# stm32.net
KiCad netlist of a schematic drawn in Altium Designer
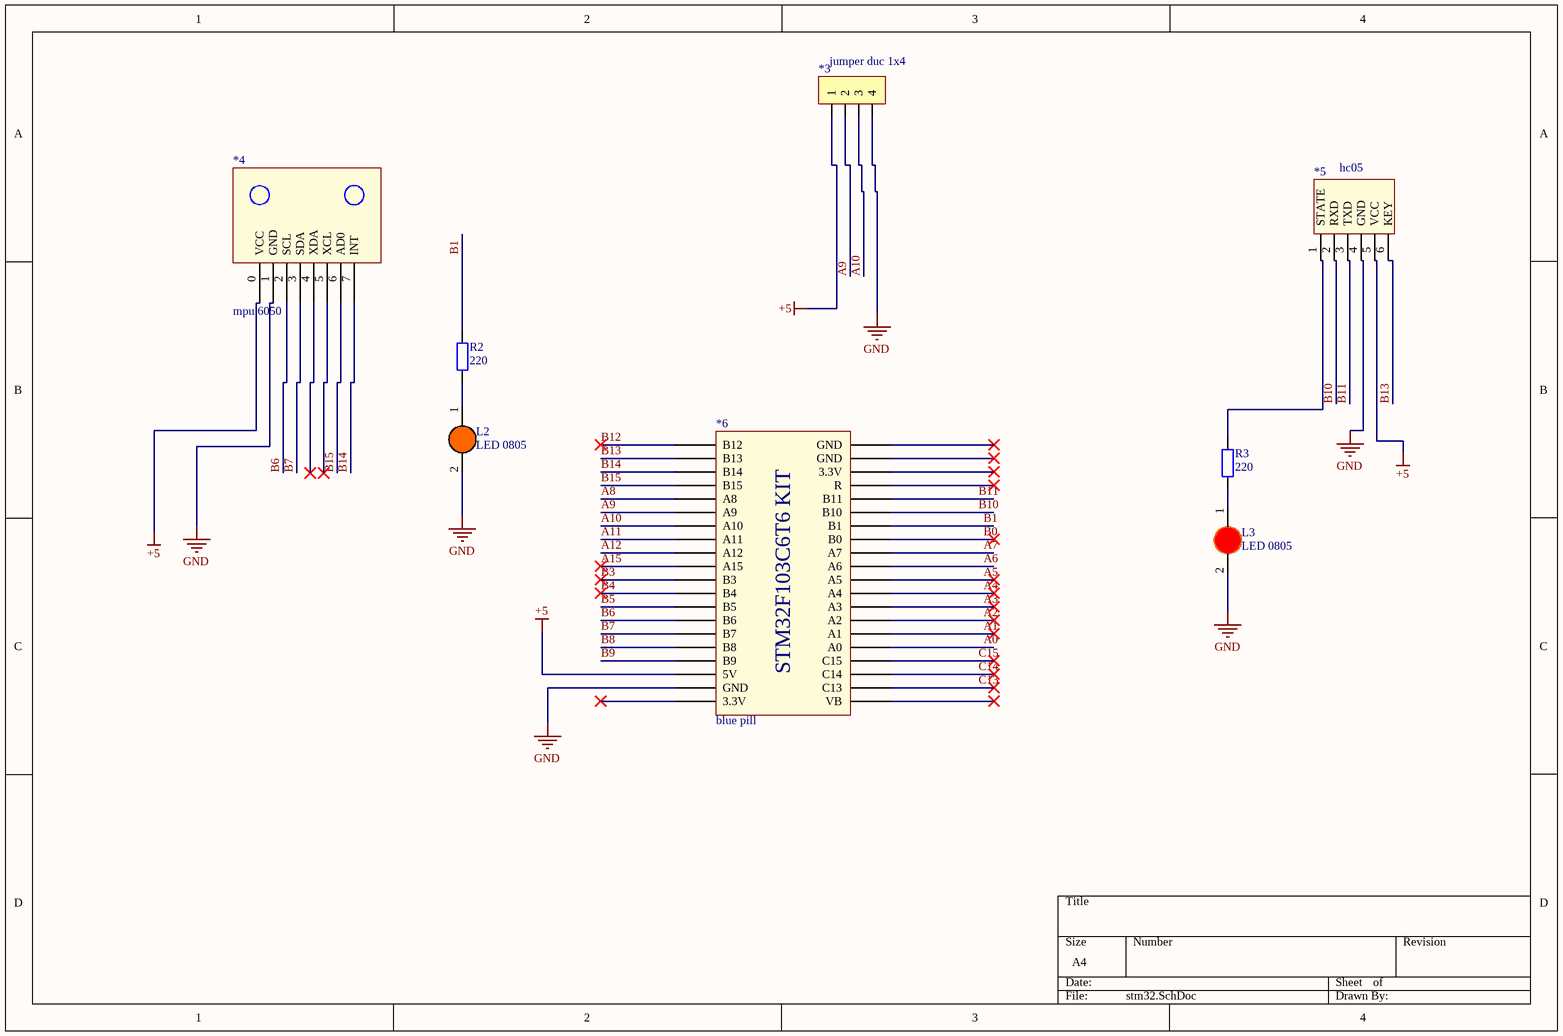
[diagram p0: stm32.SchDoc]

(export (version "E")
  (design (tool "Eeschema 10.0.6"))
  (components
    (comp (ref "*3")
      (value "jumper duc 1x4")
      (footprint "jumper cai 1x4")
      (libsource (lib "my_lib") (part "jumper duc 1x4"))
    )
    (comp (ref "*4") (value "mpu 6050") (footprint "MPU 6050") (libsource (lib "my_lib") (part "mpu 6050")))
    (comp (ref "*5") (value "hc05") (footprint "HC05") (libsource (lib "my_lib") (part "hc05")))
    (comp (ref "*6")
      (value "blue pill")
      (footprint "blue pill")
      (libsource (lib "my_lib") (part "blue pill"))
    )
    (comp (ref "L2")
      (value "LED 0805")
      (footprint "LED-0805-Orange")
      (description "Dán")
      (libsource (lib "Altium_Lib_by_KhueNguyenCreator") (part "LED 0805 Cam"))
    )
    (comp (ref "L3")
      (value "LED 0805")
      (footprint "LED-0805-Red")
      (description "Dán")
      (libsource (lib "Altium_Lib_by_KhueNguyenCreator") (part "LED 0805 Do"))
    )
    (comp (ref "R2")
      (value "220")
      (footprint "tro smd 0805")
      (description "Dán")
      (libsource (lib "Altium_Lib_by_KhueNguyenCreator") (part "Tro 0805 1% 1k"))
    )
    (comp (ref "R3")
      (value "220")
      (footprint "tro smd 0805")
      (description "Dán")
      (libsource (lib "Altium_Lib_by_KhueNguyenCreator") (part "Tro 0805 1% 1k"))
    )
  )
  (nets
    (net (code "1") (name "+5") (class "Default")
      (node (ref "*3") (pin "1") (pinfunction "1_1") (pintype "passive"))
      (node (ref "*4") (pin "0") (pinfunction "VCC_0") (pintype "passive"))
      (node (ref "*5") (pin "5") (pinfunction "VCC_5") (pintype "passive"))
      (node (ref "*6") (pin "18") (pinfunction "5V_18") (pintype "passive"))
    )
    (net (code "2") (name "/A0") (class "Default")
      (node (ref "*6") (pin "25") (pinfunction "A0_25") (pintype "passive"))
    )
    (net (code "3") (name "/A1") (class "Default")
      (node (ref "*6") (pin "26") (pinfunction "A1_26") (pintype "passive+no_connect"))
    )
    (net (code "4") (name "/A2") (class "Default")
      (node (ref "*6") (pin "27") (pinfunction "A2_27") (pintype "passive+no_connect"))
    )
    (net (code "5") (name "/A3") (class "Default")
      (node (ref "*6") (pin "28") (pinfunction "A3_28") (pintype "passive+no_connect"))
    )
    (net (code "6") (name "/A4") (class "Default")
      (node (ref "*6") (pin "29") (pinfunction "A4_29") (pintype "passive+no_connect"))
    )
    (net (code "7") (name "/A5") (class "Default")
      (node (ref "*6") (pin "30") (pinfunction "A5_30") (pintype "passive+no_connect"))
    )
    (net (code "8") (name "/A6") (class "Default")
      (node (ref "*6") (pin "31") (pinfunction "A6_31") (pintype "passive"))
    )
    (net (code "9") (name "/A7") (class "Default")
      (node (ref "*6") (pin "32") (pinfunction "A7_32") (pintype "passive"))
    )
    (net (code "10") (name "/A8") (class "Default")
      (node (ref "*6") (pin "5") (pinfunction "A8_5") (pintype "passive"))
    )
    (net (code "11") (name "/A9") (class "Default")
      (node (ref "*3") (pin "2") (pinfunction "2_2") (pintype "passive"))
      (node (ref "*6") (pin "6") (pinfunction "A9_6") (pintype "passive"))
    )
    (net (code "12") (name "/A10") (class "Default")
      (node (ref "*3") (pin "3") (pinfunction "3_3") (pintype "passive"))
      (node (ref "*6") (pin "7") (pinfunction "A10_7") (pintype "passive"))
    )
    (net (code "13") (name "/A11") (class "Default")
      (node (ref "*6") (pin "8") (pinfunction "A11_8") (pintype "passive"))
    )
    (net (code "14") (name "/A12") (class "Default")
      (node (ref "*6") (pin "9") (pinfunction "A12_9") (pintype "passive"))
    )
    (net (code "15") (name "/A15") (class "Default")
      (node (ref "*6") (pin "10") (pinfunction "A15_10") (pintype "passive+no_connect"))
    )
    (net (code "16") (name "/B0") (class "Default")
      (node (ref "*6") (pin "33") (pinfunction "B0_33") (pintype "passive+no_connect"))
    )
    (net (code "17") (name "/B1") (class "Default")
      (node (ref "*6") (pin "34") (pinfunction "B1_34") (pintype "passive"))
      (node (ref "R2") (pin "2") (pinfunction "2_2") (pintype "passive"))
    )
    (net (code "18") (name "/B3") (class "Default")
      (node (ref "*6") (pin "11") (pinfunction "B3_11") (pintype "passive+no_connect"))
    )
    (net (code "19") (name "/B4") (class "Default")
      (node (ref "*6") (pin "12") (pinfunction "B4_12") (pintype "passive+no_connect"))
    )
    (net (code "20") (name "/B5") (class "Default")
      (node (ref "*6") (pin "13") (pinfunction "B5_13") (pintype "passive"))
    )
    (net (code "21") (name "/B6") (class "Default")
      (node (ref "*4") (pin "2") (pinfunction "SCL_2") (pintype "passive"))
      (node (ref "*6") (pin "14") (pinfunction "B6_14") (pintype "passive"))
    )
    (net (code "22") (name "/B7") (class "Default")
      (node (ref "*4") (pin "3") (pinfunction "SDA_3") (pintype "passive"))
      (node (ref "*6") (pin "15") (pinfunction "B7_15") (pintype "passive"))
    )
    (net (code "23") (name "/B8") (class "Default")
      (node (ref "*6") (pin "16") (pinfunction "B8_16") (pintype "passive"))
    )
    (net (code "24") (name "/B9") (class "Default")
      (node (ref "*6") (pin "17") (pinfunction "B9_17") (pintype "passive"))
    )
    (net (code "25") (name "/B10") (class "Default")
      (node (ref "*5") (pin "2") (pinfunction "RXD_2") (pintype "passive"))
      (node (ref "*6") (pin "35") (pinfunction "B10_35") (pintype "passive"))
    )
    (net (code "26") (name "/B11") (class "Default")
      (node (ref "*5") (pin "3") (pinfunction "TXD_3") (pintype "passive"))
      (node (ref "*6") (pin "36") (pinfunction "B11_36") (pintype "passive"))
    )
    (net (code "27") (name "/B12") (class "Default")
      (node (ref "*6") (pin "1") (pinfunction "B12_1") (pintype "passive+no_connect"))
    )
    (net (code "28") (name "/B13") (class "Default")
      (node (ref "*5") (pin "6") (pinfunction "KEY_6") (pintype "passive"))
      (node (ref "*6") (pin "2") (pinfunction "B13_2") (pintype "passive"))
    )
    (net (code "29") (name "/B14") (class "Default")
      (node (ref "*4") (pin "7") (pinfunction "INT_7") (pintype "passive"))
      (node (ref "*6") (pin "3") (pinfunction "B14_3") (pintype "passive"))
    )
    (net (code "30") (name "/B15") (class "Default")
      (node (ref "*4") (pin "6") (pinfunction "AD0_6") (pintype "passive"))
      (node (ref "*6") (pin "4") (pinfunction "B15_4") (pintype "passive"))
    )
    (net (code "31") (name "/C13") (class "Default")
      (node (ref "*6") (pin "22") (pinfunction "C13_22") (pintype "passive+no_connect"))
    )
    (net (code "32") (name "/C14") (class "Default")
      (node (ref "*6") (pin "23") (pinfunction "C14_23") (pintype "passive+no_connect"))
    )
    (net (code "33") (name "/C15") (class "Default")
      (node (ref "*6") (pin "24") (pinfunction "C15_24") (pintype "passive+no_connect"))
    )
    (net (code "34") (name "GND") (class "Default")
      (node (ref "*3") (pin "4") (pinfunction "4_4") (pintype "passive"))
      (node (ref "*4") (pin "1") (pinfunction "GND_1") (pintype "passive"))
      (node (ref "*5") (pin "4") (pinfunction "GND_4") (pintype "passive"))
      (node (ref "*6") (pin "19") (pinfunction "GND_19") (pintype "passive"))
      (node (ref "L2") (pin "2") (pinfunction "K_2") (pintype "passive"))
      (node (ref "L3") (pin "2") (pinfunction "K_2") (pintype "passive"))
    )
    (net (code "35") (name "Net-(*5-STATE)") (class "Default")
      (node (ref "*5") (pin "1") (pinfunction "STATE_1") (pintype "passive"))
      (node (ref "R3") (pin "2") (pinfunction "2_2") (pintype "passive"))
    )
    (net (code "36") (name "Net-(L2-A)") (class "Default")
      (node (ref "L2") (pin "1") (pinfunction "A_1") (pintype "passive"))
      (node (ref "R2") (pin "1") (pinfunction "1_1") (pintype "passive"))
    )
    (net (code "37") (name "Net-(L3-A)") (class "Default")
      (node (ref "L3") (pin "1") (pinfunction "A_1") (pintype "passive"))
      (node (ref "R3") (pin "1") (pinfunction "1_1") (pintype "passive"))
    )
    (net (code "38") (name "unconnected-(*4-XCL-Pad5)") (class "Default")
      (node (ref "*4") (pin "5") (pinfunction "XCL_5") (pintype "passive+no_connect"))
    )
    (net (code "39") (name "unconnected-(*4-XDA-Pad4)") (class "Default")
      (node (ref "*4") (pin "4") (pinfunction "XDA_4") (pintype "passive+no_connect"))
    )
    (net (code "40") (name "unconnected-(*6-3.3V-Pad20)") (class "Default")
      (node (ref "*6") (pin "20") (pinfunction "3.3V_20") (pintype "passive+no_connect"))
    )
    (net (code "41") (name "unconnected-(*6-3.3V-Pad38)") (class "Default")
      (node (ref "*6") (pin "38") (pinfunction "3.3V_38") (pintype "passive+no_connect"))
    )
    (net (code "42") (name "unconnected-(*6-GND-Pad39)") (class "Default")
      (node (ref "*6") (pin "39") (pinfunction "GND_39") (pintype "passive+no_connect"))
    )
    (net (code "43") (name "unconnected-(*6-GND-Pad40)") (class "Default")
      (node (ref "*6") (pin "40") (pinfunction "GND_40") (pintype "passive+no_connect"))
    )
    (net (code "44") (name "unconnected-(*6-R-Pad37)") (class "Default")
      (node (ref "*6") (pin "37") (pinfunction "R_37") (pintype "passive+no_connect"))
    )
    (net (code "45") (name "unconnected-(*6-VB-Pad21)") (class "Default")
      (node (ref "*6") (pin "21") (pinfunction "VB_21") (pintype "passive+no_connect"))
    )
  )
)
